# Power_Regulator.net
KiCad netlist of a schematic drawn in Altium Designer
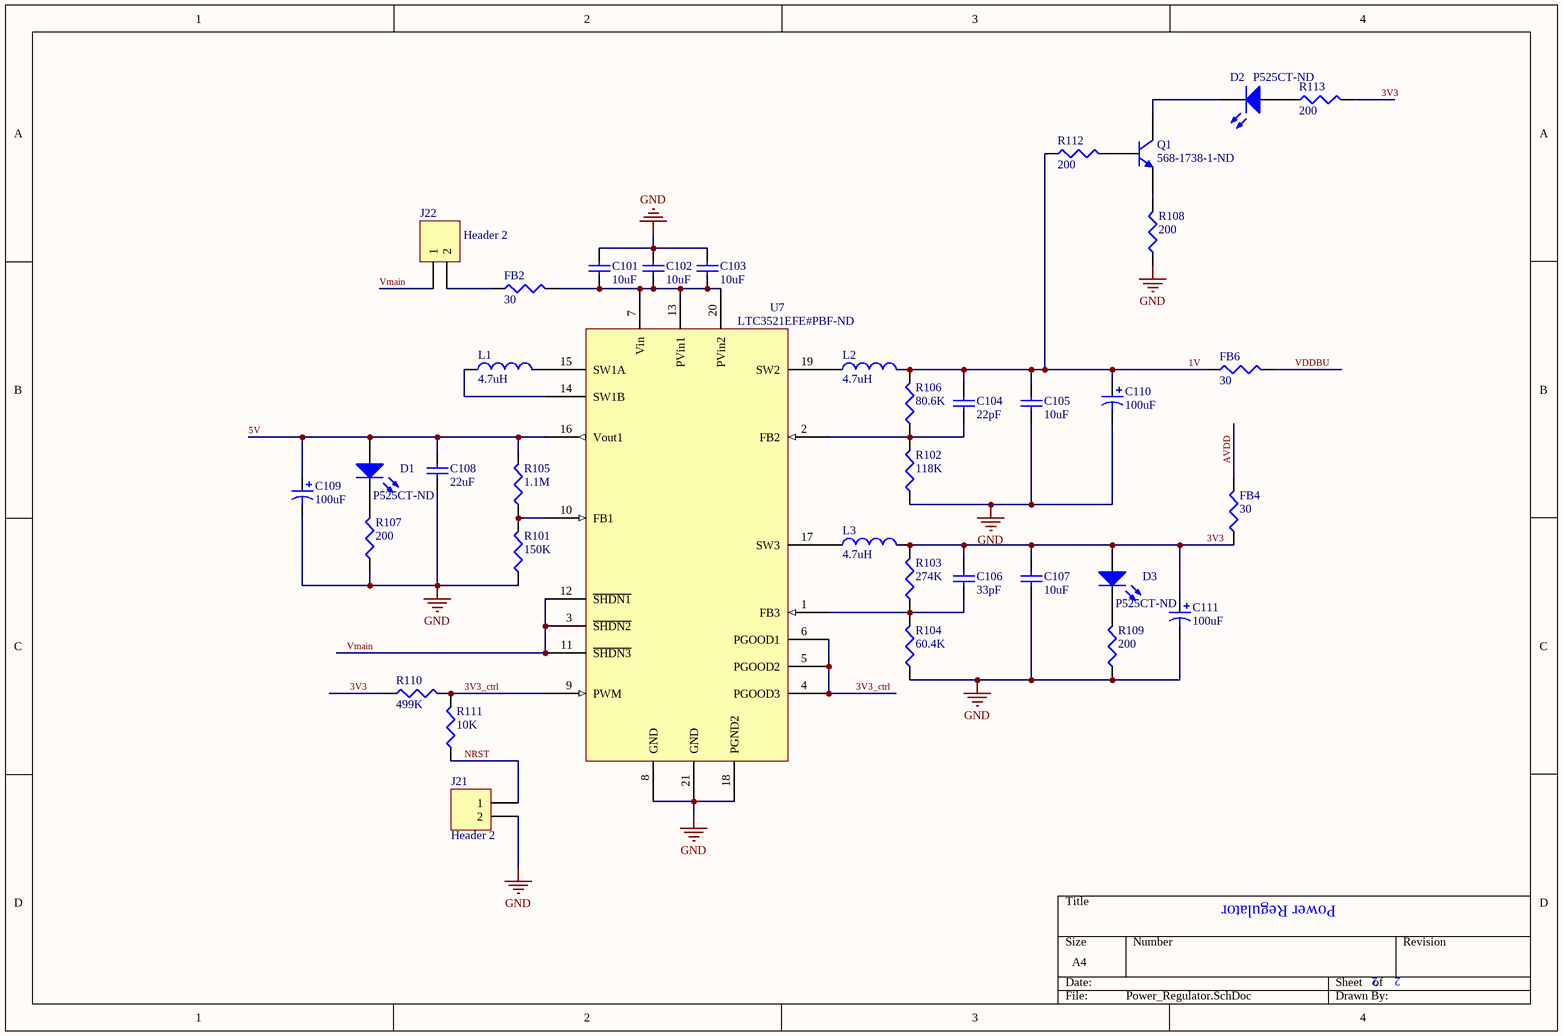
[diagram p0: Power_Regulator.SchDoc]

(export (version "E")
  (design (tool "Eeschema 10.0.6"))
  (components
    (comp (ref "C101")
      (value "10uF")
      (footprint "0805")
      (description "Ceramic Chip Capacitor - 10uF")
      (fields (field (name "Comment") "C0805_c_10uF") (field (name "PUBLISHER") "Altium Limited"))
      (libsource (lib "my_KEMET") (part "C0805_c_10uF"))
    )
    (comp (ref "C102")
      (value "10uF")
      (footprint "0805")
      (description "Ceramic Chip Capacitor - 10uF")
      (fields (field (name "Comment") "C0805_c_10uF") (field (name "PUBLISHER") "Altium Limited"))
      (libsource (lib "my_KEMET") (part "C0805_c_10uF"))
    )
    (comp (ref "C103")
      (value "10uF")
      (footprint "0805")
      (description "Ceramic Chip Capacitor - 10uF")
      (fields (field (name "Comment") "C0805_c_10uF") (field (name "PUBLISHER") "Altium Limited"))
      (libsource (lib "my_KEMET") (part "C0805_c_10uF"))
    )
    (comp (ref "C104")
      (value "22pF")
      (footprint "CAPC2008X06N")
      (description "CAP CER 22PF 50V 5% NP0 0805")
      (fields (field (name "Comment") "AVX_0805_a2_22pf"))
      (libsource (lib "Capacitors") (part "AVX_0805_a2_22pf"))
    )
    (comp (ref "C105")
      (value "10uF")
      (footprint "0805")
      (description "Ceramic Chip Capacitor - 10uF")
      (fields (field (name "Comment") "C0805_c_10uF") (field (name "PUBLISHER") "Altium Limited"))
      (libsource (lib "my_KEMET") (part "C0805_c_10uF"))
    )
    (comp (ref "C106")
      (value "33pF")
      (footprint "CAPC2008X06N")
      (description "CAP CER 33PF 50V 5% NP0 0805")
      (fields (field (name "Comment") "AVX_0805_a3_33pf"))
      (libsource (lib "Capacitors") (part "AVX_0805_a3_33pf"))
    )
    (comp (ref "C107")
      (value "10uF")
      (footprint "0805")
      (description "Ceramic Chip Capacitor - 10uF")
      (fields (field (name "Comment") "C0805_c_10uF") (field (name "PUBLISHER") "Altium Limited"))
      (libsource (lib "my_KEMET") (part "C0805_c_10uF"))
    )
    (comp (ref "C108")
      (value "22uF")
      (footprint "0805")
      (description "Ceramic Chip Capacitor - 22uF")
      (fields (field (name "Comment") "C0805_c_22uF") (field (name "PUBLISHER") "Altium Limited"))
      (libsource (lib "my_KEMET") (part "C0805_c_22uF"))
    )
    (comp (ref "C109")
      (value "100uF")
      (footprint "6032")
      (description "CAP TANT 100UF 10V 10% LOESR SMD")
      (fields (field (name "Comment") "TantCap_6032_100uF"))
      (libsource (lib "my_KEMET") (part "TantCap_6032_100uF"))
    )
    (comp (ref "C110")
      (value "100uF")
      (footprint "6032")
      (description "CAP TANT 100UF 10V 10% LOESR SMD")
      (fields (field (name "Comment") "TantCap_6032_100uF"))
      (libsource (lib "my_KEMET") (part "TantCap_6032_100uF"))
    )
    (comp (ref "C111")
      (value "100uF")
      (footprint "6032")
      (description "CAP TANT 100UF 10V 10% LOESR SMD")
      (fields (field (name "Comment") "TantCap_6032_100uF"))
      (libsource (lib "my_KEMET") (part "TantCap_6032_100uF"))
    )
    (comp (ref "D1")
      (value "LED_Green")
      (footprint "LED")
      (description "LED GREEN HI BRT SS TYPE LO CUR")
      (fields (field (name "MANUFACTURER") "Panasonic") (field (name "SUPPLIER PART NUMBER 1") "P525CT-ND"))
      (libsource (lib "LED") (part "LED_Green"))
    )
    (comp (ref "D2")
      (value "LED_Green")
      (footprint "LED")
      (description "LED GREEN HI BRT SS TYPE LO CUR")
      (fields (field (name "MANUFACTURER") "Panasonic") (field (name "SUPPLIER PART NUMBER 1") "P525CT-ND"))
      (libsource (lib "LED") (part "LED_Green"))
    )
    (comp (ref "D3")
      (value "LED_Green")
      (footprint "LED")
      (description "LED GREEN HI BRT SS TYPE LO CUR")
      (fields (field (name "MANUFACTURER") "Panasonic") (field (name "SUPPLIER PART NUMBER 1") "P525CT-ND"))
      (libsource (lib "LED") (part "LED_Green"))
    )
    (comp (ref "FB2")
      (value "Murata_a_0805_30_Ohm_100Mhz")
      (footprint "0805")
      (description "FERRITE CHIP 30 OHM 3000MA 0805")
      (fields (field (name "VALUE @ 100MHZ") "30"))
      (libsource (lib "Filters") (part "Murata_a_0805_30_Ohm_100Mhz"))
    )
    (comp (ref "FB4")
      (value "Murata_a_0805_30_Ohm_100Mhz")
      (footprint "0805")
      (description "FERRITE CHIP 30 OHM 3000MA 0805")
      (fields (field (name "VALUE @ 100MHZ") "30"))
      (libsource (lib "Filters") (part "Murata_a_0805_30_Ohm_100Mhz"))
    )
    (comp (ref "FB6")
      (value "Murata_a_0805_30_Ohm_100Mhz")
      (footprint "0805")
      (description "FERRITE CHIP 30 OHM 3000MA 0805")
      (fields (field (name "VALUE @ 100MHZ") "30"))
      (libsource (lib "Filters") (part "Murata_a_0805_30_Ohm_100Mhz"))
    )
    (comp (ref "J21")
      (value "Header 2")
      (footprint "HDR1X2")
      (description "Header, 2-Pin")
      (fields (field (name "PUBLISHER") "Altium Limited"))
      (libsource (lib "Miscellaneous Connectors") (part "Header 2"))
    )
    (comp (ref "J22")
      (value "Header 2")
      (footprint "HDR1X2")
      (description "Header, 2-Pin")
      (fields (field (name "PUBLISHER") "Altium Limited"))
      (libsource (lib "") (part "Header 2_1"))
    )
    (comp (ref "L1")
      (value "4.7uH")
      (footprint "L1812")
      (description "Inductor unshielded 4.7mH 1812 SMD")
      (fields (field (name "Comment") "L1812_4.7uH"))
      (libsource (lib "API Delevan") (part "L1812_4.7uH"))
    )
    (comp (ref "L2")
      (value "4.7uH")
      (footprint "L1812")
      (description "Inductor unshielded 4.7mH 1812 SMD")
      (fields (field (name "Comment") "L1812_4.7uH"))
      (libsource (lib "API Delevan") (part "L1812_4.7uH"))
    )
    (comp (ref "L3")
      (value "4.7uH")
      (footprint "L1812")
      (description "Inductor unshielded 4.7mH 1812 SMD")
      (fields (field (name "Comment") "L1812_4.7uH"))
      (libsource (lib "API Delevan") (part "L1812_4.7uH"))
    )
    (comp (ref "Q1")
      (value "NPN Transistor")
      (footprint "SOT95P230X110-3N")
      (description "NPN Transistor, SMD")
      (fields (field (name "SUPPLIER PART NUMBER 1") "568-1738-1-ND"))
      (libsource (lib "NXP Semiconductors") (part "NPN Transistor"))
    )
    (comp (ref "R101")
      (value "150K")
      (footprint "RES0805")
      (description "RES 150K OHM 1/8W .1% 0805 SMD")
      (fields (field (name "Comment") "Panasonic_0805_b_150K"))
      (libsource (lib "Resistors") (part "Panasonic_0805_b_150K"))
    )
    (comp (ref "R102")
      (value "118K")
      (footprint "RES0805")
      (description "RES 118K OHM 1/10W .5% 0805 SMD")
      (fields (field (name "Comment") "Susumu_0805_c_118K"))
      (libsource (lib "Resistors") (part "Susumu_0805_c_118K"))
    )
    (comp (ref "R103")
      (value "274K")
      (footprint "RES0805")
      (description "RES 274K OHM 1/10W 0.1% 0805")
      (fields (field (name "Comment") "TE_0805_a_274K"))
      (libsource (lib "Resistors") (part "TE_0805_a_274K"))
    )
    (comp (ref "R104")
      (value "60.4K")
      (footprint "RES0805")
      (description "RES 60.4K OHM 1/10W .5% 0805 SMD")
      (fields (field (name "Comment") "Susumu_0805_a_60.4K"))
      (libsource (lib "Resistors") (part "Susumu_0805_a_60.4K"))
    )
    (comp (ref "R105")
      (value "1.1M")
      (footprint "RES0805")
      (description "RES 1.1M OHM 1/16W 0.1% 0805")
      (fields (field (name "Comment") "TE_0805_c_1.1K"))
      (libsource (lib "Resistors") (part "TE_0805_c_1.1K"))
    )
    (comp (ref "R106")
      (value "80.6K")
      (footprint "RES0805")
      (description "RES 80.6K OHM 1/10W .5% 0805 SMD")
      (fields (field (name "Comment") "Susumu_0805_b_80.6K"))
      (libsource (lib "Resistors") (part "Susumu_0805_b_80.6K"))
    )
    (comp (ref "R107")
      (value "200")
      (footprint "RES0805")
      (description "RES 200 OHM 1/10W .5% 0805 SMD")
      (fields (field (name "Comment") "Susumu_0805_a3_200"))
      (libsource (lib "Resistors") (part "Susumu_0805_a3_200"))
    )
    (comp (ref "R108")
      (value "200")
      (footprint "RES0805")
      (description "RES 200 OHM 1/10W .5% 0805 SMD")
      (fields (field (name "Comment") "Susumu_0805_a3_200"))
      (libsource (lib "Resistors") (part "Susumu_0805_a3_200"))
    )
    (comp (ref "R109")
      (value "200")
      (footprint "RES0805")
      (description "RES 200 OHM 1/10W .5% 0805 SMD")
      (fields (field (name "Comment") "Susumu_0805_a3_200"))
      (libsource (lib "Resistors") (part "Susumu_0805_a3_200"))
    )
    (comp (ref "R110")
      (value "499K")
      (footprint "RES0805")
      (description "RES 499K OHM 1/10W .5% 0805 SMD")
      (fields (field (name "Comment") "Susumu_0805_c3_499K"))
      (libsource (lib "Resistors") (part "Susumu_0805_c3_499K"))
    )
    (comp (ref "R111")
      (value "10K")
      (footprint "RES0805")
      (description "RES 10.0K OHM 1/10W .5% 0805 SMD")
      (fields (field (name "Comment") "Susumu_0805_b2_10K"))
      (libsource (lib "Resistors") (part "Susumu_0805_b2_10K"))
    )
    (comp (ref "R112")
      (value "200")
      (footprint "RES0805")
      (description "RES 200 OHM 1/10W .5% 0805 SMD")
      (fields (field (name "Comment") "Susumu_0805_a3_200"))
      (libsource (lib "Resistors") (part "Susumu_0805_a3_200"))
    )
    (comp (ref "R113")
      (value "200")
      (footprint "RES0805")
      (description "RES 200 OHM 1/10W .5% 0805 SMD")
      (fields (field (name "Comment") "Susumu_0805_a3_200"))
      (libsource (lib "Resistors") (part "Susumu_0805_a3_200"))
    )
    (comp (ref "U7")
      (value "LTC3521EFE#PBF")
      (footprint "LTC3521EFE#PBF - duplicate")
      (description "IC BUCK BOOST SYNC ADJ 20TSSOP")
      (fields (field (name "SUPPLIER PART NUMBER 1") "LTC3521EFE#PBF-ND"))
      (libsource (lib "Linear Technology") (part "LTC3521EFE#PBF"))
    )
  )
  (nets
    (net (code "1") (name "/1V") (class "Default")
      (node (ref "C104") (pin "2") (pinfunction "2_2") (pintype "passive"))
      (node (ref "C105") (pin "2") (pinfunction "2_2") (pintype "passive"))
      (node (ref "C110") (pin "1") (pinfunction "1_1") (pintype "passive"))
      (node (ref "FB6") (pin "1") (pinfunction "1_1") (pintype "passive"))
      (node (ref "L2") (pin "2") (pinfunction "2_2") (pintype "passive"))
      (node (ref "R106") (pin "2") (pinfunction "2_2") (pintype "passive"))
      (node (ref "R112") (pin "1") (pinfunction "1_1") (pintype "passive"))
    )
    (net (code "2") (name "/3V3") (class "Default")
      (node (ref "C106") (pin "2") (pinfunction "2_2") (pintype "passive"))
      (node (ref "C107") (pin "2") (pinfunction "2_2") (pintype "passive"))
      (node (ref "C111") (pin "1") (pinfunction "1_1") (pintype "passive"))
      (node (ref "D3") (pin "1") (pinfunction "A_1") (pintype "passive"))
      (node (ref "FB4") (pin "1") (pinfunction "1_1") (pintype "passive"))
      (node (ref "L3") (pin "2") (pinfunction "2_2") (pintype "passive"))
      (node (ref "R103") (pin "2") (pinfunction "2_2") (pintype "passive"))
      (node (ref "R110") (pin "1") (pinfunction "1_1") (pintype "passive"))
      (node (ref "R113") (pin "2") (pinfunction "2_2") (pintype "passive"))
    )
    (net (code "3") (name "/3V3_ctrl") (class "Default")
      (node (ref "R110") (pin "2") (pinfunction "2_2") (pintype "passive"))
      (node (ref "R111") (pin "2") (pinfunction "2_2") (pintype "passive"))
      (node (ref "U7") (pin "4") (pinfunction "PGOOD3_4") (pintype "open_collector"))
      (node (ref "U7") (pin "5") (pinfunction "PGOOD2_5") (pintype "open_collector"))
      (node (ref "U7") (pin "6") (pinfunction "PGOOD1_6") (pintype "open_collector"))
      (node (ref "U7") (pin "9") (pinfunction "PWM_9") (pintype "input"))
    )
    (net (code "4") (name "/5V") (class "Default")
      (node (ref "C108") (pin "2") (pinfunction "2_2") (pintype "passive"))
      (node (ref "C109") (pin "1") (pinfunction "1_1") (pintype "passive"))
      (node (ref "D1") (pin "1") (pinfunction "A_1") (pintype "passive"))
      (node (ref "R105") (pin "2") (pinfunction "2_2") (pintype "passive"))
      (node (ref "U7") (pin "16") (pinfunction "Vout1_16") (pintype "output"))
    )
    (net (code "5") (name "/AVDD") (class "Default")
      (node (ref "FB4") (pin "2") (pinfunction "2_2") (pintype "passive"))
    )
    (net (code "6") (name "/NRST") (class "Default")
      (node (ref "J21") (pin "1") (pinfunction "1_1") (pintype "passive"))
      (node (ref "R111") (pin "1") (pinfunction "1_1") (pintype "passive"))
    )
    (net (code "7") (name "/VDDBU") (class "Default")
      (node (ref "FB6") (pin "2") (pinfunction "2_2") (pintype "passive"))
    )
    (net (code "8") (name "/Vmain") (class "Default")
      (node (ref "J22") (pin "1") (pinfunction "1_1") (pintype "passive"))
      (node (ref "U7") (pin "11") (pinfunction "~{SHDN3}_11") (pintype "passive"))
      (node (ref "U7") (pin "12") (pinfunction "~{SHDN1}_12") (pintype "passive"))
      (node (ref "U7") (pin "3") (pinfunction "~{SHDN2}_3") (pintype "passive"))
    )
    (net (code "9") (name "GND") (class "Default")
      (node (ref "C101") (pin "2") (pinfunction "2_2") (pintype "passive"))
      (node (ref "C102") (pin "2") (pinfunction "2_2") (pintype "passive"))
      (node (ref "C103") (pin "2") (pinfunction "2_2") (pintype "passive"))
      (node (ref "C105") (pin "1") (pinfunction "1_1") (pintype "passive"))
      (node (ref "C107") (pin "1") (pinfunction "1_1") (pintype "passive"))
      (node (ref "C108") (pin "1") (pinfunction "1_1") (pintype "passive"))
      (node (ref "C109") (pin "2") (pinfunction "2_2") (pintype "passive"))
      (node (ref "C110") (pin "2") (pinfunction "2_2") (pintype "passive"))
      (node (ref "C111") (pin "2") (pinfunction "2_2") (pintype "passive"))
      (node (ref "J21") (pin "2") (pinfunction "2_2") (pintype "passive"))
      (node (ref "R101") (pin "1") (pinfunction "1_1") (pintype "passive"))
      (node (ref "R102") (pin "1") (pinfunction "1_1") (pintype "passive"))
      (node (ref "R104") (pin "1") (pinfunction "1_1") (pintype "passive"))
      (node (ref "R107") (pin "1") (pinfunction "1_1") (pintype "passive"))
      (node (ref "R108") (pin "1") (pinfunction "1_1") (pintype "passive"))
      (node (ref "R109") (pin "1") (pinfunction "1_1") (pintype "passive"))
      (node (ref "U7") (pin "18") (pinfunction "PGND2_18") (pintype "passive"))
      (node (ref "U7") (pin "21") (pinfunction "GND_21") (pintype "passive"))
      (node (ref "U7") (pin "8") (pinfunction "GND_8") (pintype "passive"))
    )
    (net (code "10") (name "Net-(D1-K)") (class "Default")
      (node (ref "D1") (pin "2") (pinfunction "K_2") (pintype "passive"))
      (node (ref "R107") (pin "2") (pinfunction "2_2") (pintype "passive"))
    )
    (net (code "11") (name "Net-(D2-A)") (class "Default")
      (node (ref "D2") (pin "1") (pinfunction "A_1") (pintype "passive"))
      (node (ref "R113") (pin "1") (pinfunction "1_1") (pintype "passive"))
    )
    (net (code "12") (name "Net-(D2-K)") (class "Default")
      (node (ref "D2") (pin "2") (pinfunction "K_2") (pintype "passive"))
      (node (ref "Q1") (pin "3") (pinfunction "C_3") (pintype "passive"))
    )
    (net (code "13") (name "Net-(D3-K)") (class "Default")
      (node (ref "D3") (pin "2") (pinfunction "K_2") (pintype "passive"))
      (node (ref "R109") (pin "2") (pinfunction "2_2") (pintype "passive"))
    )
    (net (code "14") (name "Net-(FB2-Pad1)") (class "Default")
      (node (ref "FB2") (pin "1") (pinfunction "1_1") (pintype "passive"))
      (node (ref "J22") (pin "2") (pinfunction "2_2") (pintype "passive"))
    )
    (net (code "15") (name "Net-(Q1-B)") (class "Default")
      (node (ref "Q1") (pin "1") (pinfunction "B_1") (pintype "passive"))
      (node (ref "R112") (pin "2") (pinfunction "2_2") (pintype "passive"))
    )
    (net (code "16") (name "Net-(Q1-E)") (class "Default")
      (node (ref "Q1") (pin "2") (pinfunction "E_2") (pintype "passive"))
      (node (ref "R108") (pin "2") (pinfunction "2_2") (pintype "passive"))
    )
    (net (code "17") (name "Net-(U7-FB1)") (class "Default")
      (node (ref "R101") (pin "2") (pinfunction "2_2") (pintype "passive"))
      (node (ref "R105") (pin "1") (pinfunction "1_1") (pintype "passive"))
      (node (ref "U7") (pin "10") (pinfunction "FB1_10") (pintype "input"))
    )
    (net (code "18") (name "Net-(U7-FB2)") (class "Default")
      (node (ref "C104") (pin "1") (pinfunction "1_1") (pintype "passive"))
      (node (ref "R102") (pin "2") (pinfunction "2_2") (pintype "passive"))
      (node (ref "R106") (pin "1") (pinfunction "1_1") (pintype "passive"))
      (node (ref "U7") (pin "2") (pinfunction "FB2_2") (pintype "input"))
    )
    (net (code "19") (name "Net-(U7-FB3)") (class "Default")
      (node (ref "C106") (pin "1") (pinfunction "1_1") (pintype "passive"))
      (node (ref "R103") (pin "1") (pinfunction "1_1") (pintype "passive"))
      (node (ref "R104") (pin "2") (pinfunction "2_2") (pintype "passive"))
      (node (ref "U7") (pin "1") (pinfunction "FB3_1") (pintype "input"))
    )
    (net (code "20") (name "Net-(U7-PVin1)") (class "Default")
      (node (ref "C101") (pin "1") (pinfunction "1_1") (pintype "passive"))
      (node (ref "C102") (pin "1") (pinfunction "1_1") (pintype "passive"))
      (node (ref "C103") (pin "1") (pinfunction "1_1") (pintype "passive"))
      (node (ref "FB2") (pin "2") (pinfunction "2_2") (pintype "passive"))
      (node (ref "U7") (pin "13") (pinfunction "PVin1_13") (pintype "power_in"))
      (node (ref "U7") (pin "20") (pinfunction "PVin2_20") (pintype "power_in"))
      (node (ref "U7") (pin "7") (pinfunction "Vin_7") (pintype "power_in"))
    )
    (net (code "21") (name "Net-(U7-SW1A)") (class "Default")
      (node (ref "L1") (pin "2") (pinfunction "2_2") (pintype "passive"))
      (node (ref "U7") (pin "15") (pinfunction "SW1A_15") (pintype "passive"))
    )
    (net (code "22") (name "Net-(U7-SW1B)") (class "Default")
      (node (ref "L1") (pin "1") (pinfunction "1_1") (pintype "passive"))
      (node (ref "U7") (pin "14") (pinfunction "SW1B_14") (pintype "passive"))
    )
    (net (code "23") (name "Net-(U7-SW2)") (class "Default")
      (node (ref "L2") (pin "1") (pinfunction "1_1") (pintype "passive"))
      (node (ref "U7") (pin "19") (pinfunction "SW2_19") (pintype "passive"))
    )
    (net (code "24") (name "Net-(U7-SW3)") (class "Default")
      (node (ref "L3") (pin "1") (pinfunction "1_1") (pintype "passive"))
      (node (ref "U7") (pin "17") (pinfunction "SW3_17") (pintype "passive"))
    )
  )
)
